# EMMC_with_RK3399.net
KiCad netlist of a schematic drawn in Altium Designer
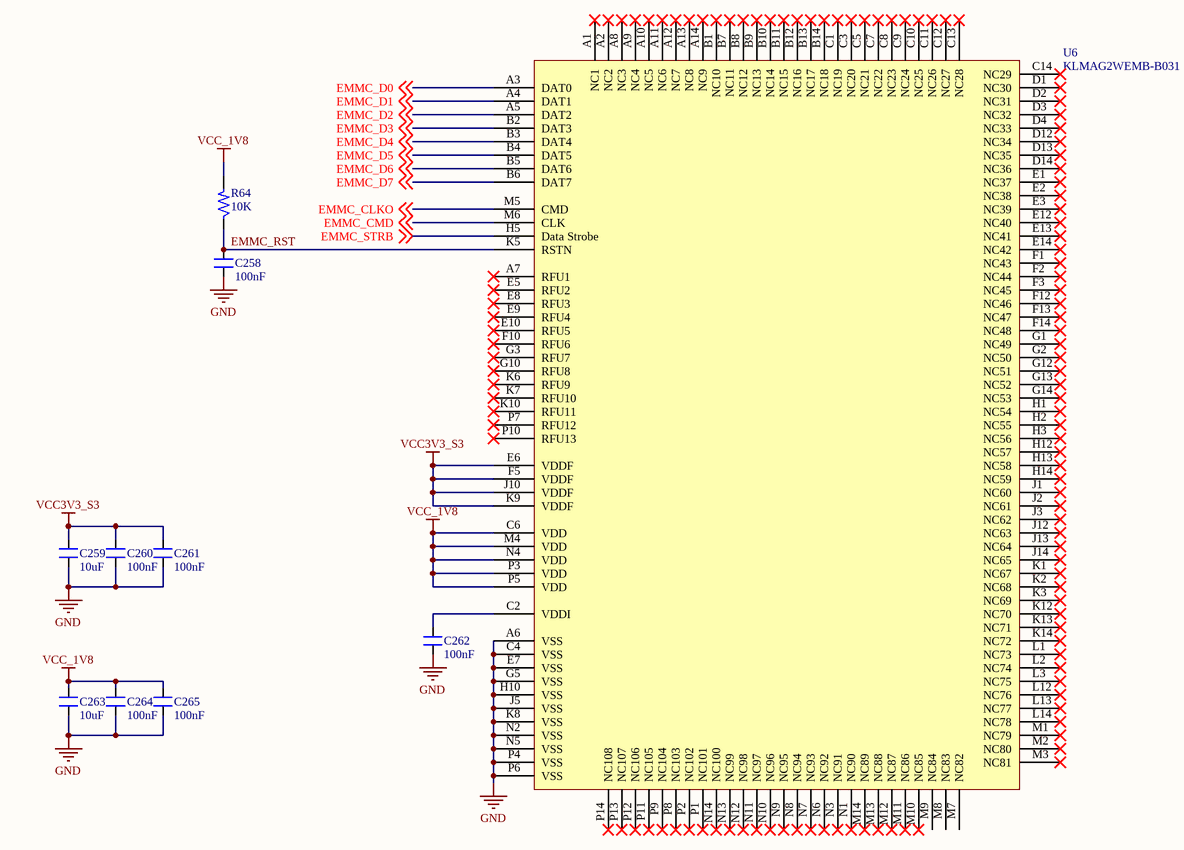
[diagram p0: EMMC with RK3399.SchDoc]

(export (version "E")
  (design (tool "Eeschema 10.0.6"))
  (components
    (comp (ref "C258")
      (value "100nF")
      (footprint "CAP_0201")
      (description "0.1µF ±10% 25V Ceramic Capacitor X5R 0201 (0603 Metric)")
      (fields
        (field (name "MANUFACTURER") "TDK Corporation")
        (field (name "MANUFACTURER PART NUMBER") "C0603X5R1E104K030BB")
      )
      (libsource (lib "EsteemPCB_SOM_Course_intlib") (part "CAP_100nF-25V-10%-0201"))
    )
    (comp (ref "C259")
      (value "10uF")
      (footprint "CAP_0402")
      (description "10µF ±20% 10V Ceramic Capacitor X5R 0402 (1005 Metric)")
      (fields
        (field (name "MANUFACTURER PART NUMBER") "CL05A106MP5NUNC")
        (field (name "MANUFACTURER") "Samsung Electro-Mechanics")
      )
      (libsource (lib "EsteemPCB_SOM_Course_intlib") (part "CAP_10uF-10V-20%-0402"))
    )
    (comp (ref "C260")
      (value "100nF")
      (footprint "CAP_0201")
      (description "0.1µF ±10% 25V Ceramic Capacitor X5R 0201 (0603 Metric)")
      (fields
        (field (name "MANUFACTURER") "TDK Corporation")
        (field (name "MANUFACTURER PART NUMBER") "C0603X5R1E104K030BB")
      )
      (libsource (lib "EsteemPCB_SOM_Course_intlib") (part "CAP_100nF-25V-10%-0201"))
    )
    (comp (ref "C261")
      (value "100nF")
      (footprint "CAP_0201")
      (description "0.1µF ±10% 25V Ceramic Capacitor X5R 0201 (0603 Metric)")
      (fields
        (field (name "MANUFACTURER") "TDK Corporation")
        (field (name "MANUFACTURER PART NUMBER") "C0603X5R1E104K030BB")
      )
      (libsource (lib "EsteemPCB_SOM_Course_intlib") (part "CAP_100nF-25V-10%-0201"))
    )
    (comp (ref "C262")
      (value "100nF")
      (footprint "CAP_0201")
      (description "0.1µF ±10% 25V Ceramic Capacitor X5R 0201 (0603 Metric)")
      (fields
        (field (name "MANUFACTURER") "TDK Corporation")
        (field (name "MANUFACTURER PART NUMBER") "C0603X5R1E104K030BB")
      )
      (libsource (lib "EsteemPCB_SOM_Course_intlib") (part "CAP_100nF-25V-10%-0201"))
    )
    (comp (ref "C263")
      (value "10uF")
      (footprint "CAP_0402")
      (description "10µF ±20% 10V Ceramic Capacitor X5R 0402 (1005 Metric)")
      (fields
        (field (name "MANUFACTURER PART NUMBER") "CL05A106MP5NUNC")
        (field (name "MANUFACTURER") "Samsung Electro-Mechanics")
      )
      (libsource (lib "EsteemPCB_SOM_Course_intlib") (part "CAP_10uF-10V-20%-0402"))
    )
    (comp (ref "C264")
      (value "100nF")
      (footprint "CAP_0201")
      (description "0.1µF ±10% 25V Ceramic Capacitor X5R 0201 (0603 Metric)")
      (fields
        (field (name "MANUFACTURER") "TDK Corporation")
        (field (name "MANUFACTURER PART NUMBER") "C0603X5R1E104K030BB")
      )
      (libsource (lib "EsteemPCB_SOM_Course_intlib") (part "CAP_100nF-25V-10%-0201"))
    )
    (comp (ref "C265")
      (value "100nF")
      (footprint "CAP_0201")
      (description "0.1µF ±10% 25V Ceramic Capacitor X5R 0201 (0603 Metric)")
      (fields
        (field (name "MANUFACTURER") "TDK Corporation")
        (field (name "MANUFACTURER PART NUMBER") "C0603X5R1E104K030BB")
      )
      (libsource (lib "EsteemPCB_SOM_Course_intlib") (part "CAP_100nF-25V-10%-0201"))
    )
    (comp (ref "R64")
      (value "10K")
      (footprint "RES_0201")
      (description "10 kOhms ±1% 0.05W, 1/20W Chip Resistor 0201 (0603 Metric) Thick Film")
      (fields
        (field (name "MANUFACTURER") "Stackpole Electronics Inc")
        (field (name "MANUFACTURER PART NUMBER") "RMCF0201FT10K0")
      )
      (libsource (lib "EsteemPCB_SOM_Course_intlib") (part "RES_10K-0.05W-1%-0201"))
    )
    (comp (ref "U6")
      (value "KLMAG2WEMB-B031")
      (footprint "BGA153C50P14X14_1150X1300X70")
      (description "16GB NAND Flash Memory")
      (fields (field (name "MANUFACTURER") "Samsung Electronics"))
      (libsource (lib "EsteemPCB_SOM_Course_intlib") (part "IC_KLMAG2WEMB-B031"))
    )
  )
  (nets
    (net (code "1") (name "/EMMC_RST") (class "Default")
      (node (ref "C258") (pin "2") (pinfunction "2_2") (pintype "passive"))
      (node (ref "R64") (pin "1") (pinfunction "1_1") (pintype "passive"))
      (node (ref "U6") (pin "K5") (pinfunction "RSTN_K5") (pintype "passive"))
    )
    (net (code "2") (name "EMMC_CLKO") (class "Default")
      (node (ref "U6") (pin "M5") (pinfunction "CMD_M5") (pintype "passive"))
    )
    (net (code "3") (name "EMMC_CMD") (class "Default")
      (node (ref "U6") (pin "M6") (pinfunction "CLK_M6") (pintype "passive"))
    )
    (net (code "4") (name "EMMC_D0") (class "Default")
      (node (ref "U6") (pin "A3") (pinfunction "DAT0_A3") (pintype "passive"))
    )
    (net (code "5") (name "EMMC_D1") (class "Default")
      (node (ref "U6") (pin "A4") (pinfunction "DAT1_A4") (pintype "passive"))
    )
    (net (code "6") (name "EMMC_D2") (class "Default")
      (node (ref "U6") (pin "A5") (pinfunction "DAT2_A5") (pintype "passive"))
    )
    (net (code "7") (name "EMMC_D3") (class "Default")
      (node (ref "U6") (pin "B2") (pinfunction "DAT3_B2") (pintype "passive"))
    )
    (net (code "8") (name "EMMC_D4") (class "Default")
      (node (ref "U6") (pin "B3") (pinfunction "DAT4_B3") (pintype "passive"))
    )
    (net (code "9") (name "EMMC_D5") (class "Default")
      (node (ref "U6") (pin "B4") (pinfunction "DAT5_B4") (pintype "passive"))
    )
    (net (code "10") (name "EMMC_D6") (class "Default")
      (node (ref "U6") (pin "B5") (pinfunction "DAT6_B5") (pintype "passive"))
    )
    (net (code "11") (name "EMMC_D7") (class "Default")
      (node (ref "U6") (pin "B6") (pinfunction "DAT7_B6") (pintype "passive"))
    )
    (net (code "12") (name "EMMC_STRB") (class "Default")
      (node (ref "U6") (pin "H5") (pinfunction "Data_Strobe_H5") (pintype "passive"))
    )
    (net (code "13") (name "GND") (class "Default")
      (node (ref "C258") (pin "1") (pinfunction "1_1") (pintype "passive"))
      (node (ref "C259") (pin "1") (pinfunction "1_1") (pintype "passive"))
      (node (ref "C260") (pin "1") (pinfunction "1_1") (pintype "passive"))
      (node (ref "C261") (pin "1") (pinfunction "1_1") (pintype "passive"))
      (node (ref "C262") (pin "1") (pinfunction "1_1") (pintype "passive"))
      (node (ref "C263") (pin "1") (pinfunction "1_1") (pintype "passive"))
      (node (ref "C264") (pin "1") (pinfunction "1_1") (pintype "passive"))
      (node (ref "C265") (pin "1") (pinfunction "1_1") (pintype "passive"))
      (node (ref "U6") (pin "A6") (pinfunction "VSS_A6") (pintype "passive"))
      (node (ref "U6") (pin "C4") (pinfunction "VSS_C4") (pintype "passive"))
      (node (ref "U6") (pin "E7") (pinfunction "VSS_E7") (pintype "passive"))
      (node (ref "U6") (pin "G5") (pinfunction "VSS_G5") (pintype "passive"))
      (node (ref "U6") (pin "H10") (pinfunction "VSS_H10") (pintype "passive"))
      (node (ref "U6") (pin "J5") (pinfunction "VSS_J5") (pintype "passive"))
      (node (ref "U6") (pin "K8") (pinfunction "VSS_K8") (pintype "passive"))
      (node (ref "U6") (pin "N2") (pinfunction "VSS_N2") (pintype "passive"))
      (node (ref "U6") (pin "N5") (pinfunction "VSS_N5") (pintype "passive"))
      (node (ref "U6") (pin "P4") (pinfunction "VSS_P4") (pintype "passive"))
      (node (ref "U6") (pin "P6") (pinfunction "VSS_P6") (pintype "passive"))
    )
    (net (code "14") (name "Net-(U6-VDDI)") (class "Default")
      (node (ref "C262") (pin "2") (pinfunction "2_2") (pintype "passive"))
      (node (ref "U6") (pin "C2") (pinfunction "VDDI_C2") (pintype "passive"))
    )
    (net (code "15") (name "VCC3V3_S3") (class "Default")
      (node (ref "C259") (pin "2") (pinfunction "2_2") (pintype "passive"))
      (node (ref "C260") (pin "2") (pinfunction "2_2") (pintype "passive"))
      (node (ref "C261") (pin "2") (pinfunction "2_2") (pintype "passive"))
      (node (ref "U6") (pin "E6") (pinfunction "VDDF_E6") (pintype "passive"))
      (node (ref "U6") (pin "F5") (pinfunction "VDDF_F5") (pintype "passive"))
      (node (ref "U6") (pin "J10") (pinfunction "VDDF_J10") (pintype "passive"))
      (node (ref "U6") (pin "K9") (pinfunction "VDDF_K9") (pintype "passive"))
    )
    (net (code "16") (name "VCC_1V8") (class "Default")
      (node (ref "C263") (pin "2") (pinfunction "2_2") (pintype "passive"))
      (node (ref "C264") (pin "2") (pinfunction "2_2") (pintype "passive"))
      (node (ref "C265") (pin "2") (pinfunction "2_2") (pintype "passive"))
      (node (ref "R64") (pin "2") (pinfunction "2_2") (pintype "passive"))
      (node (ref "U6") (pin "C6") (pinfunction "VDD_C6") (pintype "passive"))
      (node (ref "U6") (pin "M4") (pinfunction "VDD_M4") (pintype "passive"))
      (node (ref "U6") (pin "N4") (pinfunction "VDD_N4") (pintype "passive"))
      (node (ref "U6") (pin "P3") (pinfunction "VDD_P3") (pintype "passive"))
      (node (ref "U6") (pin "P5") (pinfunction "VDD_P5") (pintype "passive"))
    )
    (net (code "17") (name "unconnected-(U6-NC1-PadA1)") (class "Default")
      (node (ref "U6") (pin "A1") (pinfunction "NC1_A1") (pintype "passive+no_connect"))
    )
    (net (code "18") (name "unconnected-(U6-NC2-PadA2)") (class "Default")
      (node (ref "U6") (pin "A2") (pinfunction "NC2_A2") (pintype "passive+no_connect"))
    )
    (net (code "19") (name "unconnected-(U6-NC3-PadA8)") (class "Default")
      (node (ref "U6") (pin "A8") (pinfunction "NC3_A8") (pintype "passive+no_connect"))
    )
    (net (code "20") (name "unconnected-(U6-NC4-PadA9)") (class "Default")
      (node (ref "U6") (pin "A9") (pinfunction "NC4_A9") (pintype "passive+no_connect"))
    )
    (net (code "21") (name "unconnected-(U6-NC5-PadA10)") (class "Default")
      (node (ref "U6") (pin "A10") (pinfunction "NC5_A10") (pintype "passive+no_connect"))
    )
    (net (code "22") (name "unconnected-(U6-NC6-PadA11)") (class "Default")
      (node (ref "U6") (pin "A11") (pinfunction "NC6_A11") (pintype "passive+no_connect"))
    )
    (net (code "23") (name "unconnected-(U6-NC7-PadA12)") (class "Default")
      (node (ref "U6") (pin "A12") (pinfunction "NC7_A12") (pintype "passive+no_connect"))
    )
    (net (code "24") (name "unconnected-(U6-NC8-PadA13)") (class "Default")
      (node (ref "U6") (pin "A13") (pinfunction "NC8_A13") (pintype "passive+no_connect"))
    )
    (net (code "25") (name "unconnected-(U6-NC9-PadA14)") (class "Default")
      (node (ref "U6") (pin "A14") (pinfunction "NC9_A14") (pintype "passive+no_connect"))
    )
    (net (code "26") (name "unconnected-(U6-NC10-PadB1)") (class "Default")
      (node (ref "U6") (pin "B1") (pinfunction "NC10_B1") (pintype "passive+no_connect"))
    )
    (net (code "27") (name "unconnected-(U6-NC11-PadB7)") (class "Default")
      (node (ref "U6") (pin "B7") (pinfunction "NC11_B7") (pintype "passive+no_connect"))
    )
    (net (code "28") (name "unconnected-(U6-NC12-PadB8)") (class "Default")
      (node (ref "U6") (pin "B8") (pinfunction "NC12_B8") (pintype "passive+no_connect"))
    )
    (net (code "29") (name "unconnected-(U6-NC13-PadB9)") (class "Default")
      (node (ref "U6") (pin "B9") (pinfunction "NC13_B9") (pintype "passive+no_connect"))
    )
    (net (code "30") (name "unconnected-(U6-NC14-PadB10)") (class "Default")
      (node (ref "U6") (pin "B10") (pinfunction "NC14_B10") (pintype "passive+no_connect"))
    )
    (net (code "31") (name "unconnected-(U6-NC15-PadB11)") (class "Default")
      (node (ref "U6") (pin "B11") (pinfunction "NC15_B11") (pintype "passive+no_connect"))
    )
    (net (code "32") (name "unconnected-(U6-NC16-PadB12)") (class "Default")
      (node (ref "U6") (pin "B12") (pinfunction "NC16_B12") (pintype "passive+no_connect"))
    )
    (net (code "33") (name "unconnected-(U6-NC17-PadB13)") (class "Default")
      (node (ref "U6") (pin "B13") (pinfunction "NC17_B13") (pintype "passive+no_connect"))
    )
    (net (code "34") (name "unconnected-(U6-NC18-PadB14)") (class "Default")
      (node (ref "U6") (pin "B14") (pinfunction "NC18_B14") (pintype "passive+no_connect"))
    )
    (net (code "35") (name "unconnected-(U6-NC19-PadC1)") (class "Default")
      (node (ref "U6") (pin "C1") (pinfunction "NC19_C1") (pintype "passive+no_connect"))
    )
    (net (code "36") (name "unconnected-(U6-NC20-PadC3)") (class "Default")
      (node (ref "U6") (pin "C3") (pinfunction "NC20_C3") (pintype "passive+no_connect"))
    )
    (net (code "37") (name "unconnected-(U6-NC21-PadC5)") (class "Default")
      (node (ref "U6") (pin "C5") (pinfunction "NC21_C5") (pintype "passive+no_connect"))
    )
    (net (code "38") (name "unconnected-(U6-NC22-PadC7)") (class "Default")
      (node (ref "U6") (pin "C7") (pinfunction "NC22_C7") (pintype "passive+no_connect"))
    )
    (net (code "39") (name "unconnected-(U6-NC23-PadC8)") (class "Default")
      (node (ref "U6") (pin "C8") (pinfunction "NC23_C8") (pintype "passive+no_connect"))
    )
    (net (code "40") (name "unconnected-(U6-NC24-PadC9)") (class "Default")
      (node (ref "U6") (pin "C9") (pinfunction "NC24_C9") (pintype "passive+no_connect"))
    )
    (net (code "41") (name "unconnected-(U6-NC25-PadC10)") (class "Default")
      (node (ref "U6") (pin "C10") (pinfunction "NC25_C10") (pintype "passive+no_connect"))
    )
    (net (code "42") (name "unconnected-(U6-NC26-PadC11)") (class "Default")
      (node (ref "U6") (pin "C11") (pinfunction "NC26_C11") (pintype "passive+no_connect"))
    )
    (net (code "43") (name "unconnected-(U6-NC27-PadC12)") (class "Default")
      (node (ref "U6") (pin "C12") (pinfunction "NC27_C12") (pintype "passive+no_connect"))
    )
    (net (code "44") (name "unconnected-(U6-NC28-PadC13)") (class "Default")
      (node (ref "U6") (pin "C13") (pinfunction "NC28_C13") (pintype "passive+no_connect"))
    )
    (net (code "45") (name "unconnected-(U6-NC29-PadC14)") (class "Default")
      (node (ref "U6") (pin "C14") (pinfunction "NC29_C14") (pintype "passive+no_connect"))
    )
    (net (code "46") (name "unconnected-(U6-NC30-PadD1)") (class "Default")
      (node (ref "U6") (pin "D1") (pinfunction "NC30_D1") (pintype "passive+no_connect"))
    )
    (net (code "47") (name "unconnected-(U6-NC31-PadD2)") (class "Default")
      (node (ref "U6") (pin "D2") (pinfunction "NC31_D2") (pintype "passive+no_connect"))
    )
    (net (code "48") (name "unconnected-(U6-NC32-PadD3)") (class "Default")
      (node (ref "U6") (pin "D3") (pinfunction "NC32_D3") (pintype "passive+no_connect"))
    )
    (net (code "49") (name "unconnected-(U6-NC33-PadD4)") (class "Default")
      (node (ref "U6") (pin "D4") (pinfunction "NC33_D4") (pintype "passive+no_connect"))
    )
    (net (code "50") (name "unconnected-(U6-NC34-PadD12)") (class "Default")
      (node (ref "U6") (pin "D12") (pinfunction "NC34_D12") (pintype "passive+no_connect"))
    )
    (net (code "51") (name "unconnected-(U6-NC35-PadD13)") (class "Default")
      (node (ref "U6") (pin "D13") (pinfunction "NC35_D13") (pintype "passive+no_connect"))
    )
    (net (code "52") (name "unconnected-(U6-NC36-PadD14)") (class "Default")
      (node (ref "U6") (pin "D14") (pinfunction "NC36_D14") (pintype "passive+no_connect"))
    )
    (net (code "53") (name "unconnected-(U6-NC37-PadE1)") (class "Default")
      (node (ref "U6") (pin "E1") (pinfunction "NC37_E1") (pintype "passive+no_connect"))
    )
    (net (code "54") (name "unconnected-(U6-NC38-PadE2)") (class "Default")
      (node (ref "U6") (pin "E2") (pinfunction "NC38_E2") (pintype "passive+no_connect"))
    )
    (net (code "55") (name "unconnected-(U6-NC39-PadE3)") (class "Default")
      (node (ref "U6") (pin "E3") (pinfunction "NC39_E3") (pintype "passive+no_connect"))
    )
    (net (code "56") (name "unconnected-(U6-NC40-PadE12)") (class "Default")
      (node (ref "U6") (pin "E12") (pinfunction "NC40_E12") (pintype "passive+no_connect"))
    )
    (net (code "57") (name "unconnected-(U6-NC41-PadE13)") (class "Default")
      (node (ref "U6") (pin "E13") (pinfunction "NC41_E13") (pintype "passive+no_connect"))
    )
    (net (code "58") (name "unconnected-(U6-NC42-PadE14)") (class "Default")
      (node (ref "U6") (pin "E14") (pinfunction "NC42_E14") (pintype "passive+no_connect"))
    )
    (net (code "59") (name "unconnected-(U6-NC43-PadF1)") (class "Default")
      (node (ref "U6") (pin "F1") (pinfunction "NC43_F1") (pintype "passive+no_connect"))
    )
    (net (code "60") (name "unconnected-(U6-NC44-PadF2)") (class "Default")
      (node (ref "U6") (pin "F2") (pinfunction "NC44_F2") (pintype "passive+no_connect"))
    )
    (net (code "61") (name "unconnected-(U6-NC45-PadF3)") (class "Default")
      (node (ref "U6") (pin "F3") (pinfunction "NC45_F3") (pintype "passive+no_connect"))
    )
    (net (code "62") (name "unconnected-(U6-NC46-PadF12)") (class "Default")
      (node (ref "U6") (pin "F12") (pinfunction "NC46_F12") (pintype "passive+no_connect"))
    )
    (net (code "63") (name "unconnected-(U6-NC47-PadF13)") (class "Default")
      (node (ref "U6") (pin "F13") (pinfunction "NC47_F13") (pintype "passive+no_connect"))
    )
    (net (code "64") (name "unconnected-(U6-NC48-PadF14)") (class "Default")
      (node (ref "U6") (pin "F14") (pinfunction "NC48_F14") (pintype "passive+no_connect"))
    )
    (net (code "65") (name "unconnected-(U6-NC49-PadG1)") (class "Default")
      (node (ref "U6") (pin "G1") (pinfunction "NC49_G1") (pintype "passive+no_connect"))
    )
    (net (code "66") (name "unconnected-(U6-NC50-PadG2)") (class "Default")
      (node (ref "U6") (pin "G2") (pinfunction "NC50_G2") (pintype "passive+no_connect"))
    )
    (net (code "67") (name "unconnected-(U6-NC51-PadG12)") (class "Default")
      (node (ref "U6") (pin "G12") (pinfunction "NC51_G12") (pintype "passive+no_connect"))
    )
    (net (code "68") (name "unconnected-(U6-NC52-PadG13)") (class "Default")
      (node (ref "U6") (pin "G13") (pinfunction "NC52_G13") (pintype "passive+no_connect"))
    )
    (net (code "69") (name "unconnected-(U6-NC53-PadG14)") (class "Default")
      (node (ref "U6") (pin "G14") (pinfunction "NC53_G14") (pintype "passive+no_connect"))
    )
    (net (code "70") (name "unconnected-(U6-NC54-PadH1)") (class "Default")
      (node (ref "U6") (pin "H1") (pinfunction "NC54_H1") (pintype "passive+no_connect"))
    )
    (net (code "71") (name "unconnected-(U6-NC55-PadH2)") (class "Default")
      (node (ref "U6") (pin "H2") (pinfunction "NC55_H2") (pintype "passive+no_connect"))
    )
    (net (code "72") (name "unconnected-(U6-NC56-PadH3)") (class "Default")
      (node (ref "U6") (pin "H3") (pinfunction "NC56_H3") (pintype "passive+no_connect"))
    )
    (net (code "73") (name "unconnected-(U6-NC57-PadH12)") (class "Default")
      (node (ref "U6") (pin "H12") (pinfunction "NC57_H12") (pintype "passive+no_connect"))
    )
    (net (code "74") (name "unconnected-(U6-NC58-PadH13)") (class "Default")
      (node (ref "U6") (pin "H13") (pinfunction "NC58_H13") (pintype "passive+no_connect"))
    )
    (net (code "75") (name "unconnected-(U6-NC59-PadH14)") (class "Default")
      (node (ref "U6") (pin "H14") (pinfunction "NC59_H14") (pintype "passive+no_connect"))
    )
    (net (code "76") (name "unconnected-(U6-NC60-PadJ1)") (class "Default")
      (node (ref "U6") (pin "J1") (pinfunction "NC60_J1") (pintype "passive+no_connect"))
    )
    (net (code "77") (name "unconnected-(U6-NC61-PadJ2)") (class "Default")
      (node (ref "U6") (pin "J2") (pinfunction "NC61_J2") (pintype "passive+no_connect"))
    )
    (net (code "78") (name "unconnected-(U6-NC62-PadJ3)") (class "Default")
      (node (ref "U6") (pin "J3") (pinfunction "NC62_J3") (pintype "passive+no_connect"))
    )
    (net (code "79") (name "unconnected-(U6-NC63-PadJ12)") (class "Default")
      (node (ref "U6") (pin "J12") (pinfunction "NC63_J12") (pintype "passive+no_connect"))
    )
    (net (code "80") (name "unconnected-(U6-NC64-PadJ13)") (class "Default")
      (node (ref "U6") (pin "J13") (pinfunction "NC64_J13") (pintype "passive+no_connect"))
    )
    (net (code "81") (name "unconnected-(U6-NC65-PadJ14)") (class "Default")
      (node (ref "U6") (pin "J14") (pinfunction "NC65_J14") (pintype "passive+no_connect"))
    )
    (net (code "82") (name "unconnected-(U6-NC67-PadK1)") (class "Default")
      (node (ref "U6") (pin "K1") (pinfunction "NC67_K1") (pintype "passive+no_connect"))
    )
    (net (code "83") (name "unconnected-(U6-NC68-PadK2)") (class "Default")
      (node (ref "U6") (pin "K2") (pinfunction "NC68_K2") (pintype "passive+no_connect"))
    )
    (net (code "84") (name "unconnected-(U6-NC69-PadK3)") (class "Default")
      (node (ref "U6") (pin "K3") (pinfunction "NC69_K3") (pintype "passive+no_connect"))
    )
    (net (code "85") (name "unconnected-(U6-NC70-PadK12)") (class "Default")
      (node (ref "U6") (pin "K12") (pinfunction "NC70_K12") (pintype "passive+no_connect"))
    )
    (net (code "86") (name "unconnected-(U6-NC71-PadK13)") (class "Default")
      (node (ref "U6") (pin "K13") (pinfunction "NC71_K13") (pintype "passive+no_connect"))
    )
    (net (code "87") (name "unconnected-(U6-NC72-PadK14)") (class "Default")
      (node (ref "U6") (pin "K14") (pinfunction "NC72_K14") (pintype "passive+no_connect"))
    )
    (net (code "88") (name "unconnected-(U6-NC73-PadL1)") (class "Default")
      (node (ref "U6") (pin "L1") (pinfunction "NC73_L1") (pintype "passive+no_connect"))
    )
    (net (code "89") (name "unconnected-(U6-NC74-PadL2)") (class "Default")
      (node (ref "U6") (pin "L2") (pinfunction "NC74_L2") (pintype "passive+no_connect"))
    )
    (net (code "90") (name "unconnected-(U6-NC75-PadL3)") (class "Default")
      (node (ref "U6") (pin "L3") (pinfunction "NC75_L3") (pintype "passive+no_connect"))
    )
    (net (code "91") (name "unconnected-(U6-NC76-PadL12)") (class "Default")
      (node (ref "U6") (pin "L12") (pinfunction "NC76_L12") (pintype "passive+no_connect"))
    )
    (net (code "92") (name "unconnected-(U6-NC77-PadL13)") (class "Default")
      (node (ref "U6") (pin "L13") (pinfunction "NC77_L13") (pintype "passive+no_connect"))
    )
    (net (code "93") (name "unconnected-(U6-NC78-PadL14)") (class "Default")
      (node (ref "U6") (pin "L14") (pinfunction "NC78_L14") (pintype "passive+no_connect"))
    )
    (net (code "94") (name "unconnected-(U6-NC79-PadM1)") (class "Default")
      (node (ref "U6") (pin "M1") (pinfunction "NC79_M1") (pintype "passive+no_connect"))
    )
    (net (code "95") (name "unconnected-(U6-NC80-PadM2)") (class "Default")
      (node (ref "U6") (pin "M2") (pinfunction "NC80_M2") (pintype "passive+no_connect"))
    )
    (net (code "96") (name "unconnected-(U6-NC81-PadM3)") (class "Default")
      (node (ref "U6") (pin "M3") (pinfunction "NC81_M3") (pintype "passive+no_connect"))
    )
    (net (code "97") (name "unconnected-(U6-NC82-PadM7)") (class "Default")
      (node (ref "U6") (pin "M7") (pinfunction "NC82_M7") (pintype "passive"))
    )
    (net (code "98") (name "unconnected-(U6-NC83-PadM8)") (class "Default")
      (node (ref "U6") (pin "M8") (pinfunction "NC83_M8") (pintype "passive"))
    )
    (net (code "99") (name "unconnected-(U6-NC84-PadM9)") (class "Default")
      (node (ref "U6") (pin "M9") (pinfunction "NC84_M9") (pintype "passive"))
    )
    (net (code "100") (name "unconnected-(U6-NC85-PadM10)") (class "Default")
      (node (ref "U6") (pin "M10") (pinfunction "NC85_M10") (pintype "passive+no_connect"))
    )
    (net (code "101") (name "unconnected-(U6-NC86-PadM11)") (class "Default")
      (node (ref "U6") (pin "M11") (pinfunction "NC86_M11") (pintype "passive+no_connect"))
    )
    (net (code "102") (name "unconnected-(U6-NC87-PadM12)") (class "Default")
      (node (ref "U6") (pin "M12") (pinfunction "NC87_M12") (pintype "passive+no_connect"))
    )
    (net (code "103") (name "unconnected-(U6-NC88-PadM13)") (class "Default")
      (node (ref "U6") (pin "M13") (pinfunction "NC88_M13") (pintype "passive+no_connect"))
    )
    (net (code "104") (name "unconnected-(U6-NC89-PadM14)") (class "Default")
      (node (ref "U6") (pin "M14") (pinfunction "NC89_M14") (pintype "passive+no_connect"))
    )
    (net (code "105") (name "unconnected-(U6-NC90-PadN1)") (class "Default")
      (node (ref "U6") (pin "N1") (pinfunction "NC90_N1") (pintype "passive+no_connect"))
    )
    (net (code "106") (name "unconnected-(U6-NC91-PadN3)") (class "Default")
      (node (ref "U6") (pin "N3") (pinfunction "NC91_N3") (pintype "passive+no_connect"))
    )
    (net (code "107") (name "unconnected-(U6-NC92-PadN6)") (class "Default")
      (node (ref "U6") (pin "N6") (pinfunction "NC92_N6") (pintype "passive+no_connect"))
    )
    (net (code "108") (name "unconnected-(U6-NC93-PadN7)") (class "Default")
      (node (ref "U6") (pin "N7") (pinfunction "NC93_N7") (pintype "passive+no_connect"))
    )
    (net (code "109") (name "unconnected-(U6-NC94-PadN8)") (class "Default")
      (node (ref "U6") (pin "N8") (pinfunction "NC94_N8") (pintype "passive+no_connect"))
    )
    (net (code "110") (name "unconnected-(U6-NC95-PadN9)") (class "Default")
      (node (ref "U6") (pin "N9") (pinfunction "NC95_N9") (pintype "passive+no_connect"))
    )
    (net (code "111") (name "unconnected-(U6-NC96-PadN10)") (class "Default")
      (node (ref "U6") (pin "N10") (pinfunction "NC96_N10") (pintype "passive+no_connect"))
    )
    (net (code "112") (name "unconnected-(U6-NC97-PadN11)") (class "Default")
      (node (ref "U6") (pin "N11") (pinfunction "NC97_N11") (pintype "passive+no_connect"))
    )
    (net (code "113") (name "unconnected-(U6-NC98-PadN12)") (class "Default")
      (node (ref "U6") (pin "N12") (pinfunction "NC98_N12") (pintype "passive+no_connect"))
    )
    (net (code "114") (name "unconnected-(U6-NC99-PadN13)") (class "Default")
      (node (ref "U6") (pin "N13") (pinfunction "NC99_N13") (pintype "passive+no_connect"))
    )
    (net (code "115") (name "unconnected-(U6-NC100-PadN14)") (class "Default")
      (node (ref "U6") (pin "N14") (pinfunction "NC100_N14") (pintype "passive+no_connect"))
    )
    (net (code "116") (name "unconnected-(U6-NC101-PadP1)") (class "Default")
      (node (ref "U6") (pin "P1") (pinfunction "NC101_P1") (pintype "passive+no_connect"))
    )
    (net (code "117") (name "unconnected-(U6-NC102-PadP2)") (class "Default")
      (node (ref "U6") (pin "P2") (pinfunction "NC102_P2") (pintype "passive+no_connect"))
    )
    (net (code "118") (name "unconnected-(U6-NC103-PadP8)") (class "Default")
      (node (ref "U6") (pin "P8") (pinfunction "NC103_P8") (pintype "passive+no_connect"))
    )
    (net (code "119") (name "unconnected-(U6-NC104-PadP9)") (class "Default")
      (node (ref "U6") (pin "P9") (pinfunction "NC104_P9") (pintype "passive+no_connect"))
    )
    (net (code "120") (name "unconnected-(U6-NC105-PadP11)") (class "Default")
      (node (ref "U6") (pin "P11") (pinfunction "NC105_P11") (pintype "passive+no_connect"))
    )
    (net (code "121") (name "unconnected-(U6-NC106-PadP12)") (class "Default")
      (node (ref "U6") (pin "P12") (pinfunction "NC106_P12") (pintype "passive+no_connect"))
    )
    (net (code "122") (name "unconnected-(U6-NC107-PadP13)") (class "Default")
      (node (ref "U6") (pin "P13") (pinfunction "NC107_P13") (pintype "passive+no_connect"))
    )
    (net (code "123") (name "unconnected-(U6-NC108-PadP14)") (class "Default")
      (node (ref "U6") (pin "P14") (pinfunction "NC108_P14") (pintype "passive+no_connect"))
    )
    (net (code "124") (name "unconnected-(U6-RFU1-PadA7)") (class "Default")
      (node (ref "U6") (pin "A7") (pinfunction "RFU1_A7") (pintype "passive+no_connect"))
    )
    (net (code "125") (name "unconnected-(U6-RFU2-PadE5)") (class "Default")
      (node (ref "U6") (pin "E5") (pinfunction "RFU2_E5") (pintype "passive+no_connect"))
    )
    (net (code "126") (name "unconnected-(U6-RFU3-PadE8)") (class "Default")
      (node (ref "U6") (pin "E8") (pinfunction "RFU3_E8") (pintype "passive+no_connect"))
    )
    (net (code "127") (name "unconnected-(U6-RFU4-PadE9)") (class "Default")
      (node (ref "U6") (pin "E9") (pinfunction "RFU4_E9") (pintype "passive+no_connect"))
    )
    (net (code "128") (name "unconnected-(U6-RFU5-PadE10)") (class "Default")
      (node (ref "U6") (pin "E10") (pinfunction "RFU5_E10") (pintype "passive+no_connect"))
    )
    (net (code "129") (name "unconnected-(U6-RFU6-PadF10)") (class "Default")
      (node (ref "U6") (pin "F10") (pinfunction "RFU6_F10") (pintype "passive+no_connect"))
    )
    (net (code "130") (name "unconnected-(U6-RFU7-PadG3)") (class "Default")
      (node (ref "U6") (pin "G3") (pinfunction "RFU7_G3") (pintype "passive+no_connect"))
    )
    (net (code "131") (name "unconnected-(U6-RFU8-PadG10)") (class "Default")
      (node (ref "U6") (pin "G10") (pinfunction "RFU8_G10") (pintype "passive+no_connect"))
    )
    (net (code "132") (name "unconnected-(U6-RFU9-PadK6)") (class "Default")
      (node (ref "U6") (pin "K6") (pinfunction "RFU9_K6") (pintype "passive+no_connect"))
    )
    (net (code "133") (name "unconnected-(U6-RFU10-PadK7)") (class "Default")
      (node (ref "U6") (pin "K7") (pinfunction "RFU10_K7") (pintype "passive+no_connect"))
    )
    (net (code "134") (name "unconnected-(U6-RFU11-PadK10)") (class "Default")
      (node (ref "U6") (pin "K10") (pinfunction "RFU11_K10") (pintype "passive+no_connect"))
    )
    (net (code "135") (name "unconnected-(U6-RFU12-PadP7)") (class "Default")
      (node (ref "U6") (pin "P7") (pinfunction "RFU12_P7") (pintype "passive+no_connect"))
    )
    (net (code "136") (name "unconnected-(U6-RFU13-PadP10)") (class "Default")
      (node (ref "U6") (pin "P10") (pinfunction "RFU13_P10") (pintype "passive+no_connect"))
    )
  )
)
